# Sheet1.net
KiCad netlist of a schematic drawn in Altium Designer
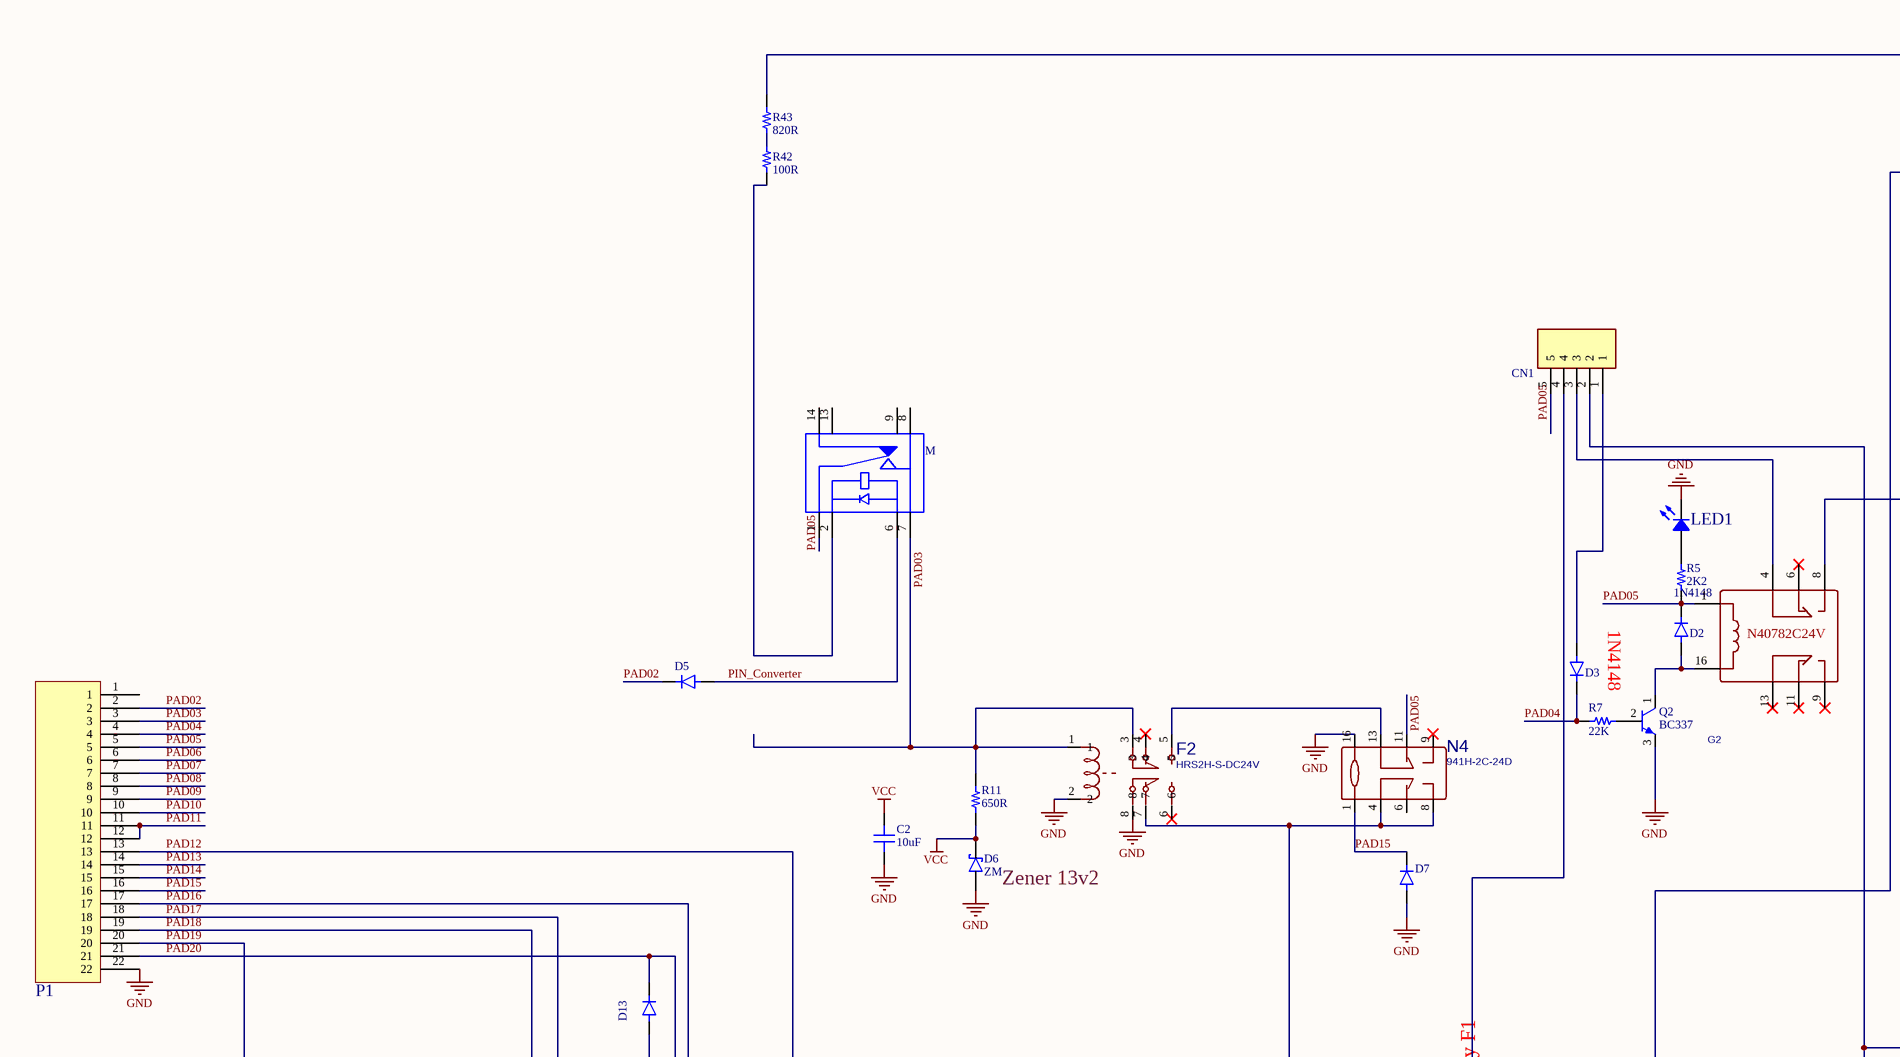
[diagram p0: Sheet1.SchDoc, top left]
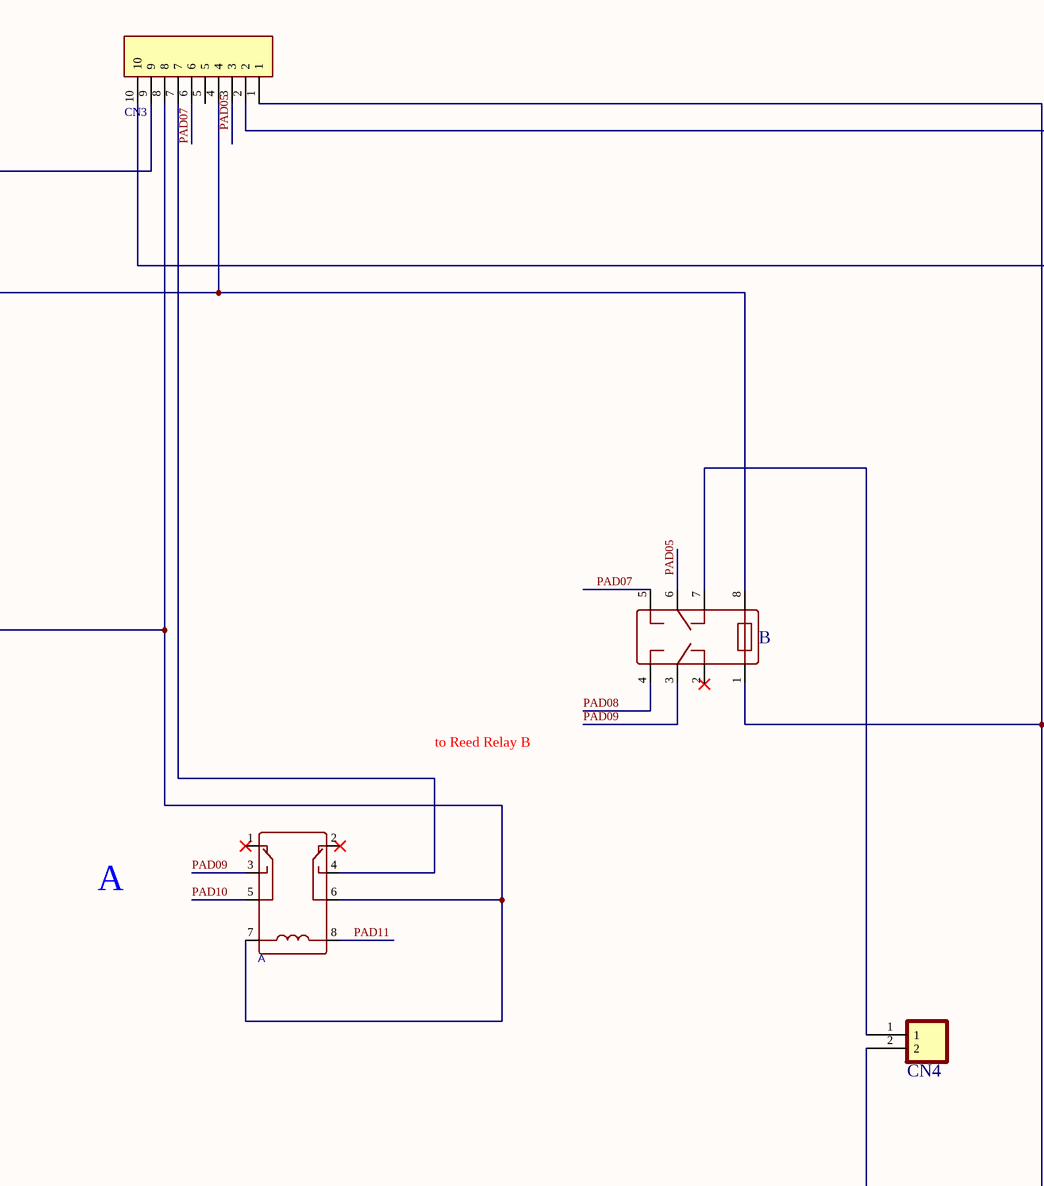
[diagram p1: Sheet1.SchDoc, top right]
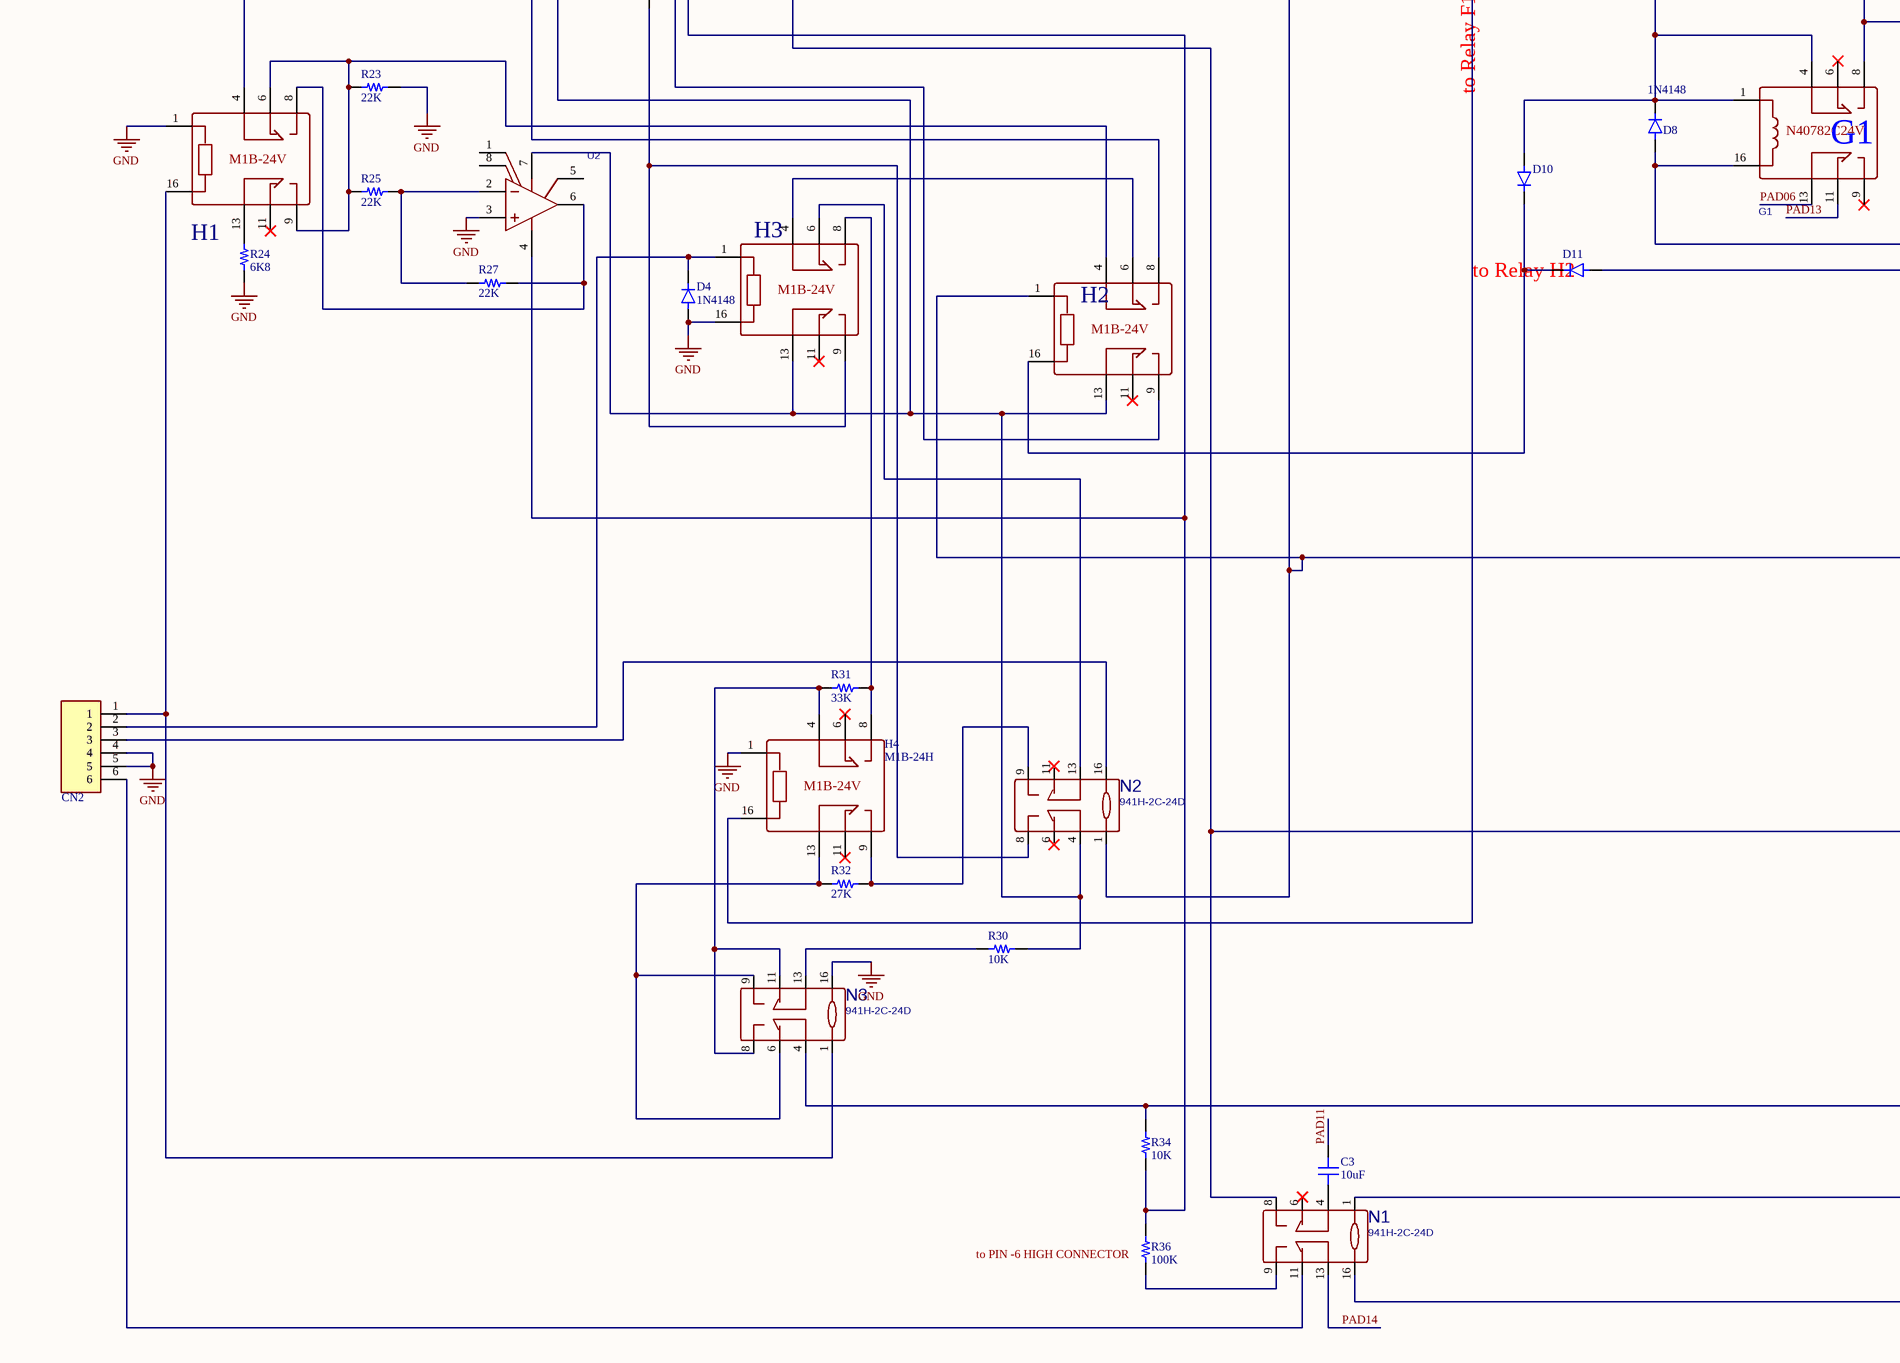
[diagram p2: Sheet1.SchDoc, bottom left]
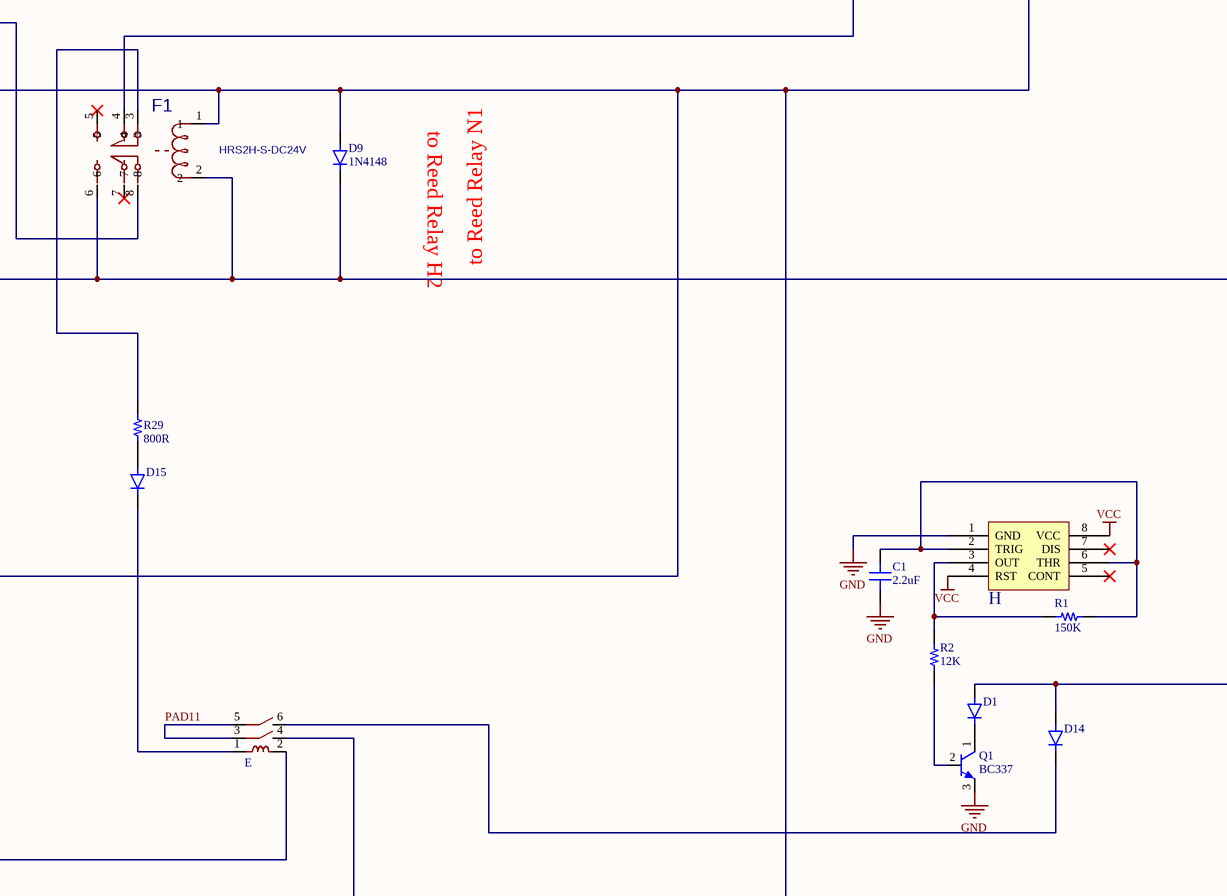
[diagram p3: Sheet1.SchDoc, bottom right]

(export (version "E")
  (design (tool "Eeschema 10.0.6"))
  (components
    (comp (ref "A")
      (value "OMRON_LY2")
      (footprint "OMRON_LY2")
      (fields
        (field (name "MANUFACTURER") "NF(福特)")
        (field (name "MANUFACTURER PART") "N40782C12V0.2W")
        (field (name "CONTRIBUTOR") "lcsc")
      )
      (libsource (lib "My Library") (part "OMRON_LY2"))
    )
    (comp (ref "B")
      (value "942H-2C-24DC")
      (footprint "942H-2C-24DC")
      (description "Relay 2C 24VDC")
      (libsource (lib "My Library") (part "942H-2C-24DC"))
    )
    (comp (ref "C1")
      (value "2.2uF")
      (footprint "Cap0805")
      (description "Cap 0805 2.2uF")
      (fields (field (name "PART NUMBER") "Cap-0805-2.2uF") (field (name "MANUFACTURER") "---"))
      (libsource (lib "My Library") (part "Unpolarised Capacitor"))
    )
    (comp (ref "C2")
      (value "10uF")
      (footprint "Cap0805")
      (description "Cap 0805 10uF")
      (fields (field (name "PART NUMBER") "Cap-0805-10uF") (field (name "MANUFACTURER") "---"))
      (libsource (lib "My Library") (part "Unpolarised Capacitor"))
    )
    (comp (ref "C3")
      (value "10uF")
      (footprint "Cap0805")
      (description "Cap 0805 10uF")
      (fields (field (name "PART NUMBER") "Cap-0805-10uF") (field (name "MANUFACTURER") "---"))
      (libsource (lib "My Library") (part "Unpolarised Capacitor"))
    )
    (comp (ref "CN1")
      (value "HDR5")
      (footprint "HDR5_F")
      (description "Pitch 2.54 mm 5PIN Femail")
      (fields (field (name "MP") "HTSW-105-14-L-S") (field (name "PART NUMBER") "PinHeader 5pin"))
      (libsource (lib "My Library") (part "HDR5_F"))
    )
    (comp (ref "CN2")
      (value "HDR6")
      (footprint "HDR6_F")
      (description "Pitch 2.54 mm")
      (fields (field (name "MP") "HTSW-106-07-S-S") (field (name "PART NUMBER") "PinHeader 6pin"))
      (libsource (lib "My Library") (part "HDR6_F"))
    )
    (comp (ref "CN3")
      (value "HDR10")
      (footprint "HDR10_F")
      (description "Pitch 2.54 mm")
      (fields (field (name "MP") "HTSW-106-07-S-S") (field (name "PART NUMBER") "PinHeader 10pin"))
      (libsource (lib "My Library") (part "HDR10_F"))
    )
    (comp (ref "CN4")
      (value "PWR_HDR_2P")
      (footprint "PWR_HDR_2P")
      (description "P-P= 3.96mm")
      (fields (field (name "PART NUMBER") "Power Connector"))
      (libsource (lib "My Library") (part "PWR_HDR_2P"))
    )
    (comp (ref "D1")
      (value "~")
      (footprint "SOD-123")
      (description "Diode Standard 75 V 300mA (DC) Through Hole DO-35 Mimi Melf")
      (fields (field (name "MP") "1N4148") (field (name "MF") "ON Semiconductor"))
      (libsource (lib "My Library") (part "Diode"))
    )
    (comp (ref "D2")
      (value "1N4148")
      (footprint "SOD-123")
      (description "Diode Standard 75 V 300mA (DC) Through Hole DO-35 Mimi Melf")
      (fields (field (name "MF") "ON Semiconductor"))
      (libsource (lib "My Library") (part "Diode"))
    )
    (comp (ref "D3")
      (value "~")
      (footprint "SOD-123")
      (description "Diode Standard 75 V 300mA (DC) Through Hole DO-35 Mimi Melf")
      (fields (field (name "MF") "ON Semiconductor") (field (name "MP") "1N4148"))
      (libsource (lib "My Library") (part "Diode"))
    )
    (comp (ref "D4")
      (value "1N4148")
      (footprint "SOD-123")
      (description "Diode Standard 75 V 300mA (DC) Through Hole DO-35 Mimi Melf")
      (fields (field (name "MF") "ON Semiconductor"))
      (libsource (lib "My Library") (part "Diode"))
    )
    (comp (ref "D5")
      (value "~")
      (footprint "SOD-123")
      (description "Diode Standard 75 V 300mA (DC) Through Hole DO-35 Mimi Melf")
      (fields (field (name "MF") "ON Semiconductor") (field (name "MP") "1N4148"))
      (libsource (lib "My Library") (part "Diode"))
    )
    (comp (ref "D6")
      (value "ZM")
      (footprint "Melf")
      (description "Zener Diode Melf")
      (fields (field (name "MP") "TMMBAT41") (field (name "MF") "STMicroelectronics"))
      (libsource (lib "My Library") (part "Zener"))
    )
    (comp (ref "D7")
      (value "~")
      (footprint "SOD-123")
      (description "Diode Standard 75 V 300mA (DC) Through Hole DO-35 Mimi Melf")
      (fields (field (name "MP") "1N4148") (field (name "MF") "ON Semiconductor"))
      (libsource (lib "My Library") (part "Diode"))
    )
    (comp (ref "D8")
      (value "1N4148")
      (footprint "SOD-123")
      (description "Diode Standard 75 V 300mA (DC) Through Hole DO-35 Mimi Melf")
      (fields (field (name "MF") "ON Semiconductor"))
      (libsource (lib "My Library") (part "Diode"))
    )
    (comp (ref "D9")
      (value "1N4148")
      (footprint "SOD-123")
      (description "Diode Standard 75 V 300mA (DC) Through Hole DO-35 Mimi Melf")
      (fields (field (name "MF") "ON Semiconductor"))
      (libsource (lib "My Library") (part "Diode"))
    )
    (comp (ref "D10")
      (value "~")
      (footprint "SOD-123")
      (description "Diode Standard 75 V 300mA (DC) Through Hole DO-35 Mimi Melf")
      (fields (field (name "MP") "1N4148") (field (name "MF") "ON Semiconductor"))
      (libsource (lib "My Library") (part "Diode"))
    )
    (comp (ref "D11")
      (value "~")
      (footprint "SOD-123")
      (description "Diode Standard 75 V 300mA (DC) Through Hole DO-35 Mimi Melf")
      (fields (field (name "MP") "1N4148") (field (name "MF") "ON Semiconductor"))
      (libsource (lib "My Library") (part "Diode"))
    )
    (comp (ref "D13")
      (value "~")
      (footprint "SOD-123")
      (description "Diode Standard 75 V 300mA (DC) Through Hole DO-35 Mimi Melf")
      (fields (field (name "MF") "ON Semiconductor") (field (name "MP") "1N4148"))
      (libsource (lib "My Library") (part "Diode"))
    )
    (comp (ref "D14")
      (value "~")
      (footprint "SOD-123")
      (description "Diode Standard 75 V 300mA (DC) Through Hole DO-35 Mimi Melf")
      (fields (field (name "MP") "1N4148") (field (name "MF") "ON Semiconductor"))
      (libsource (lib "My Library") (part "Diode"))
    )
    (comp (ref "D15")
      (value "~")
      (footprint "SOD-123")
      (description "Diode Standard 75 V 300mA (DC) Through Hole DO-35 Mimi Melf")
      (fields (field (name "MP") "1N4148") (field (name "MF") "ON Semiconductor"))
      (libsource (lib "My Library") (part "Diode"))
    )
    (comp (ref "E")
      (value "OL-C-212H")
      (footprint "ol-c-212H")
      (description "REED RELAY  2 Contact")
      (libsource (lib "My Library") (part "ol-c-212H"))
    )
    (comp (ref "F1")
      (value "HRS2H-S-DC24V")
      (footprint "HRS2H-S-DC24V")
      (fields (field (name "MANUFACTURER") "HKE(汇港)"))
      (libsource (lib "RezanFelez") (part "HRS2H-S-DC24V"))
    )
    (comp (ref "F2")
      (value "HRS2H-S-DC24V")
      (footprint "HRS2H-S-DC24V")
      (fields (field (name "MANUFACTURER") "HKE(汇港)"))
      (libsource (lib "") (part "HRS2H-S-DC24V_1"))
    )
    (comp (ref "G1")
      (value "N40782C12V0.2W")
      (footprint "N40782CXXXXX")
      (fields (field (name "MANUFACTURER") "NF(福特)") (field (name "CONTRIBUTOR") "lcsc"))
      (libsource (lib "Relay") (part "N40782C24V0.2W"))
    )
    (comp (ref "G2")
      (value "N40782C12V0.2W")
      (footprint "N40782CXXXXX")
      (fields (field (name "MANUFACTURER") "NF(福特)") (field (name "CONTRIBUTOR") "lcsc"))
      (libsource (lib "Relay") (part "N40782C24V0.2W"))
    )
    (comp (ref "H")
      (value "NE555P")
      (footprint "SOP8")
      (description "Astable or Monostable Operation")
      (fields (field (name "MANUFACTURER") "TI"))
      (libsource (lib "My Library") (part "NE555P"))
    )
    (comp (ref "H1") (value "M1B-24H") (footprint "M1B-24H") (libsource (lib "Relay") (part "M1B-24H")))
    (comp (ref "H2") (value "M1B-24H") (footprint "M1B-24H") (libsource (lib "Relay") (part "M1B-24H")))
    (comp (ref "H3") (value "M1B-24H") (footprint "M1B-24H") (libsource (lib "Relay") (part "M1B-24H")))
    (comp (ref "H4") (value "M1B-24H") (footprint "M1B-24H") (libsource (lib "Relay") (part "M1B-24H")))
    (comp (ref "LED1")
      (value "---")
      (footprint "0805 LED")
      (description "LED 0805 Red 635nm, Forward Current: 20mA, Forward Voltage: 1.7V")
      (fields (field (name "PART NUMBER") "598-8110-107F") (field (name "MANUFACTURER") "Dialight"))
      (libsource (lib "My Library") (part "LED"))
    )
    (comp (ref "M")
      (value "HE721R0510")
      (footprint "HE721R0510")
      (description "RELAY REED SPDT 250MA 5V")
      (fields (field (name "DIGI-KEY_PART_NUMBER") "F11467-ND") (field (name "MF") "Littelfuse Inc."))
      (libsource (lib "My Library") (part "HE721R0510"))
    )
    (comp (ref "N1")
      (value "941H-2C-24D")
      (footprint "941H-2C-24D")
      (fields (field (name "MANUFACTURER") "欣大") (field (name "CONTRIBUTOR") "LCSC"))
      (libsource (lib "RezanFelez") (part "941H-2C-24D"))
    )
    (comp (ref "N2")
      (value "941H-2C-24D")
      (footprint "941H-2C-24D")
      (fields (field (name "MANUFACTURER") "欣大") (field (name "CONTRIBUTOR") "LCSC"))
      (libsource (lib "RezanFelez") (part "941H-2C-24D"))
    )
    (comp (ref "N3")
      (value "941H-2C-24D")
      (footprint "941H-2C-24D")
      (fields (field (name "MANUFACTURER") "欣大") (field (name "CONTRIBUTOR") "LCSC"))
      (libsource (lib "RezanFelez") (part "941H-2C-24D"))
    )
    (comp (ref "N4")
      (value "941H-2C-24D")
      (footprint "941H-2C-24D")
      (fields (field (name "MANUFACTURER") "欣大") (field (name "CONTRIBUTOR") "LCSC"))
      (libsource (lib "RezanFelez") (part "941H-2C-24D"))
    )
    (comp (ref "P1")
      (value "PCI")
      (footprint "PCI")
      (description "normal PAD for SPARK project")
      (libsource (lib "My Library") (part "PCI"))
    )
    (comp (ref "Q1")
      (value "BC337")
      (footprint "TO92")
      (description "Transistor")
      (fields (field (name "MANUFACTURER") "Diodes-Incorporated"))
      (libsource (lib "My Library") (part "BJT-NPN"))
    )
    (comp (ref "Q2")
      (value "BC337")
      (footprint "TO92")
      (description "Transistor")
      (fields (field (name "MANUFACTURER") "Diodes-Incorporated"))
      (libsource (lib "My Library") (part "BJT-NPN"))
    )
    (comp (ref "R1")
      (value "150K")
      (footprint "Res1206")
      (description "Resistor 1206 150 Kohm")
      (fields (field (name "PART NUMBER") "Res-1206-150K"))
      (libsource (lib "My Library") (part "Resistor"))
    )
    (comp (ref "R2")
      (value "12K")
      (footprint "Res1206")
      (description "Resistor 1206 12 Kohm")
      (fields (field (name "PART NUMBER") "Res-1206-12K"))
      (libsource (lib "My Library") (part "Resistor"))
    )
    (comp (ref "R5")
      (value "2K2")
      (footprint "Res1206")
      (description "Resistor 1206 2.2 Kohm")
      (fields (field (name "PART NUMBER") "Res-1206-2K2"))
      (libsource (lib "My Library") (part "Resistor"))
    )
    (comp (ref "R7")
      (value "22K")
      (footprint "Res1206")
      (description "Resistor 1206 22 Kohm")
      (fields (field (name "PART NUMBER") "Res-1206-22K"))
      (libsource (lib "My Library") (part "Resistor"))
    )
    (comp (ref "R11")
      (value "650R")
      (footprint "Res1206")
      (description "Resistor 1206 650 ohm")
      (fields (field (name "PART NUMBER") "Res-1206-650R"))
      (libsource (lib "My Library") (part "Resistor"))
    )
    (comp (ref "R23")
      (value "22K")
      (footprint "Res1206")
      (description "Resistor 1206 22 Kohm")
      (fields (field (name "PART NUMBER") "Res-1206-22K"))
      (libsource (lib "My Library") (part "Resistor"))
    )
    (comp (ref "R24")
      (value "6K8")
      (footprint "Res1206")
      (description "Resistor 1206 6.8 Kohm")
      (fields (field (name "PART NUMBER") "Res-1206-6K8"))
      (libsource (lib "My Library") (part "Resistor"))
    )
    (comp (ref "R25")
      (value "22K")
      (footprint "Res1206")
      (description "Resistor 1206 22 Kohm")
      (fields (field (name "PART NUMBER") "Res-1206-22K"))
      (libsource (lib "My Library") (part "Resistor"))
    )
    (comp (ref "R27")
      (value "22K")
      (footprint "Res1206")
      (description "Resistor 1206 22 Kohm")
      (fields (field (name "PART NUMBER") "Res-1206-22K"))
      (libsource (lib "My Library") (part "Resistor"))
    )
    (comp (ref "R29")
      (value "800R")
      (footprint "Res1206")
      (description "Resistor 1206 800 ohm")
      (fields (field (name "PART NUMBER") "Res-1206-800R"))
      (libsource (lib "My Library") (part "Resistor"))
    )
    (comp (ref "R30")
      (value "10K")
      (footprint "Res1206")
      (description "Resistor 1206 10 Kohm")
      (fields (field (name "PART NUMBER") "Res-1206-10K") (field (name "MANUFACTURER") "---"))
      (libsource (lib "My Library") (part "Resistor"))
    )
    (comp (ref "R31")
      (value "33K")
      (footprint "Res1206")
      (description "Resistor 1206 33 Kohm")
      (fields (field (name "PART NUMBER") "Res-1206-33K"))
      (libsource (lib "My Library") (part "Resistor"))
    )
    (comp (ref "R32")
      (value "27K")
      (footprint "Res1206")
      (description "Resistor 1206 27 Kohm")
      (fields (field (name "PART NUMBER") "Res-1206-27K"))
      (libsource (lib "My Library") (part "Resistor"))
    )
    (comp (ref "R34")
      (value "10K")
      (footprint "Res1206")
      (description "Resistor 1206 10 Kohm")
      (fields (field (name "PART NUMBER") "Res-1206-10K") (field (name "MANUFACTURER") "---"))
      (libsource (lib "My Library") (part "Resistor"))
    )
    (comp (ref "R36")
      (value "100K")
      (footprint "Res1206")
      (fields (field (name "PART NUMBER") "Res-1206-100K") (field (name "MANUFACTURER") "---"))
      (libsource (lib "My Library") (part "Resistor"))
    )
    (comp (ref "R42")
      (value "100R")
      (footprint "Res1206")
      (description "Resistor 1206 100 ohm")
      (fields (field (name "PART NUMBER") "Res-1206-100R"))
      (libsource (lib "My Library") (part "Resistor"))
    )
    (comp (ref "R43")
      (value "820R")
      (footprint "Res1206")
      (description "Resistor 1206 820 ohm")
      (fields (field (name "PART NUMBER") "Res-1206-820R"))
      (libsource (lib "My Library") (part "Resistor"))
    )
    (comp (ref "U2")
      (value "OP07CP")
      (footprint "SOP8")
      (description "OPAMP")
      (fields (field (name "MANUFACTURER") "TI"))
      (libsource (lib "My Library") (part "OP07CP"))
    )
  )
  (nets
    (net (code "1") (name "/PAD02") (class "Default")
      (node (ref "D5") (pin "C") (pinfunction "C_C") (pintype "passive"))
      (node (ref "P1") (pin "2") (pinfunction "2_2") (pintype "passive"))
    )
    (net (code "2") (name "/PAD03") (class "Default")
      (node (ref "F2") (pin "1") (pinfunction "1_1") (pintype "passive"))
      (node (ref "F2") (pin "3") (pinfunction "3_3") (pintype "passive"))
      (node (ref "M") (pin "7") (pinfunction "7_7") (pintype "passive"))
      (node (ref "P1") (pin "3") (pinfunction "3_3") (pintype "passive"))
      (node (ref "R11") (pin "2") (pinfunction "2_2") (pintype "passive"))
    )
    (net (code "3") (name "/PAD04") (class "Default")
      (node (ref "D3") (pin "C") (pinfunction "C_C") (pintype "passive"))
      (node (ref "P1") (pin "4") (pinfunction "4_4") (pintype "passive"))
      (node (ref "R7") (pin "1") (pinfunction "1_1") (pintype "passive"))
    )
    (net (code "4") (name "/PAD05") (class "Default")
      (node (ref "B") (pin "6") (pinfunction "6_6") (pintype "passive"))
      (node (ref "CN1") (pin "5") (pinfunction "5_5") (pintype "passive"))
      (node (ref "CN3") (pin "3") (pinfunction "3_3") (pintype "passive"))
      (node (ref "D2") (pin "C") (pinfunction "C_C") (pintype "passive"))
      (node (ref "G2") (pin "1") (pinfunction "1_1") (pintype "passive"))
      (node (ref "M") (pin "1") (pinfunction "1_1") (pintype "passive"))
      (node (ref "N4") (pin "11") (pinfunction "11_11") (pintype "passive"))
      (node (ref "P1") (pin "5") (pinfunction "5_5") (pintype "passive"))
      (node (ref "R5") (pin "1") (pinfunction "1_1") (pintype "passive"))
    )
    (net (code "5") (name "/PAD06") (class "Default")
      (node (ref "G1") (pin "13") (pinfunction "13_13") (pintype "passive"))
      (node (ref "P1") (pin "6") (pinfunction "6_6") (pintype "passive"))
    )
    (net (code "6") (name "/PAD07") (class "Default")
      (node (ref "B") (pin "5") (pinfunction "5_5") (pintype "passive"))
      (node (ref "CN3") (pin "6") (pinfunction "6_6") (pintype "passive"))
      (node (ref "P1") (pin "7") (pinfunction "7_7") (pintype "passive"))
    )
    (net (code "7") (name "/PAD08") (class "Default")
      (node (ref "B") (pin "4") (pinfunction "4_4") (pintype "passive"))
      (node (ref "P1") (pin "8") (pinfunction "8_8") (pintype "passive"))
    )
    (net (code "8") (name "/PAD09") (class "Default")
      (node (ref "A") (pin "3") (pinfunction "3_3") (pintype "passive"))
      (node (ref "B") (pin "3") (pinfunction "3_3") (pintype "passive"))
      (node (ref "P1") (pin "9") (pinfunction "9_9") (pintype "passive"))
    )
    (net (code "9") (name "/PAD10") (class "Default")
      (node (ref "A") (pin "5") (pinfunction "5_5") (pintype "passive"))
      (node (ref "P1") (pin "10") (pinfunction "10_10") (pintype "passive"))
    )
    (net (code "10") (name "/PAD11") (class "Default")
      (node (ref "A") (pin "8") (pinfunction "8_8") (pintype "passive"))
      (node (ref "C3") (pin "2") (pinfunction "2_2") (pintype "passive"))
      (node (ref "E") (pin "3") (pinfunction "3_3") (pintype "passive"))
      (node (ref "E") (pin "5") (pinfunction "5_5") (pintype "passive"))
      (node (ref "P1") (pin "11") (pinfunction "11_11") (pintype "passive"))
      (node (ref "P1") (pin "12") (pinfunction "12_12") (pintype "passive"))
    )
    (net (code "11") (name "/PAD12") (class "Default")
      (node (ref "E") (pin "2") (pinfunction "2_2") (pintype "passive"))
      (node (ref "N1") (pin "8") (pinfunction "8_8") (pintype "passive"))
      (node (ref "P1") (pin "13") (pinfunction "13_13") (pintype "passive"))
    )
    (net (code "12") (name "/PAD13") (class "Default")
      (node (ref "G1") (pin "11") (pinfunction "11_11") (pintype "passive"))
      (node (ref "P1") (pin "14") (pinfunction "14_14") (pintype "passive"))
    )
    (net (code "13") (name "/PAD14") (class "Default")
      (node (ref "N1") (pin "13") (pinfunction "13_13") (pintype "passive"))
      (node (ref "P1") (pin "15") (pinfunction "15_15") (pintype "passive"))
    )
    (net (code "14") (name "/PAD15") (class "Default")
      (node (ref "D7") (pin "C") (pinfunction "C_C") (pintype "passive"))
      (node (ref "N4") (pin "1") (pinfunction "1_1") (pintype "passive"))
      (node (ref "P1") (pin "16") (pinfunction "16_16") (pintype "passive"))
    )
    (net (code "15") (name "/PAD16") (class "Default")
      (node (ref "P1") (pin "17") (pinfunction "17_17") (pintype "passive"))
      (node (ref "R34") (pin "2") (pinfunction "2_2") (pintype "passive"))
      (node (ref "R36") (pin "1") (pinfunction "1_1") (pintype "passive"))
      (node (ref "U2") (pin "4") (pinfunction "4_4") (pintype "passive"))
    )
    (net (code "16") (name "/PAD17") (class "Default")
      (node (ref "H2") (pin "13") (pinfunction "13_13") (pintype "passive"))
      (node (ref "H3") (pin "13") (pinfunction "13_13") (pintype "passive"))
      (node (ref "N2") (pin "4") (pinfunction "4_4") (pintype "passive"))
      (node (ref "P1") (pin "18") (pinfunction "18_18") (pintype "passive"))
      (node (ref "R30") (pin "2") (pinfunction "2_2") (pintype "passive"))
      (node (ref "U2") (pin "7") (pinfunction "7_7") (pintype "passive"))
    )
    (net (code "17") (name "/PAD18") (class "Default")
      (node (ref "H2") (pin "8") (pinfunction "8_8") (pintype "passive"))
      (node (ref "P1") (pin "19") (pinfunction "19_19") (pintype "passive"))
    )
    (net (code "18") (name "/PAD19") (class "Default")
      (node (ref "H1") (pin "4") (pinfunction "4_4") (pintype "passive"))
      (node (ref "P1") (pin "20") (pinfunction "20_20") (pintype "passive"))
    )
    (net (code "19") (name "/PAD20") (class "Default")
      (node (ref "D13") (pin "C") (pinfunction "C_C") (pintype "passive"))
      (node (ref "H2") (pin "9") (pinfunction "9_9") (pintype "passive"))
      (node (ref "P1") (pin "21") (pinfunction "21_21") (pintype "passive"))
    )
    (net (code "20") (name "/PIN_Converter") (class "Default")
      (node (ref "D5") (pin "A") (pinfunction "A_A") (pintype "passive"))
      (node (ref "M") (pin "6") (pinfunction "6_6") (pintype "passive"))
    )
    (net (code "21") (name "GND") (class "Default")
      (node (ref "C1") (pin "1") (pinfunction "1_1") (pintype "passive"))
      (node (ref "C2") (pin "1") (pinfunction "1_1") (pintype "passive"))
      (node (ref "CN2") (pin "4") (pinfunction "4_4") (pintype "passive"))
      (node (ref "CN2") (pin "5") (pinfunction "5_5") (pintype "passive"))
      (node (ref "D4") (pin "A") (pinfunction "A_A") (pintype "passive"))
      (node (ref "D6") (pin "A") (pinfunction "A_A") (pintype "passive"))
      (node (ref "D7") (pin "A") (pinfunction "A_A") (pintype "passive"))
      (node (ref "F2") (pin "2") (pinfunction "2_2") (pintype "passive"))
      (node (ref "F2") (pin "8") (pinfunction "8_8") (pintype "passive"))
      (node (ref "H") (pin "1") (pinfunction "GND_1") (pintype "passive"))
      (node (ref "H1") (pin "1") (pinfunction "1_1") (pintype "passive"))
      (node (ref "H3") (pin "16") (pinfunction "16_16") (pintype "passive"))
      (node (ref "H4") (pin "1") (pinfunction "1_1") (pintype "passive"))
      (node (ref "LED1") (pin "2") (pinfunction "2_2") (pintype "passive"))
      (node (ref "N3") (pin "16") (pinfunction "16_16") (pintype "passive"))
      (node (ref "N4") (pin "16") (pinfunction "16_16") (pintype "passive"))
      (node (ref "P1") (pin "22") (pinfunction "22_22") (pintype "passive"))
      (node (ref "Q1") (pin "3") (pinfunction "E_3") (pintype "passive"))
      (node (ref "Q2") (pin "3") (pinfunction "E_3") (pintype "passive"))
      (node (ref "R23") (pin "2") (pinfunction "2_2") (pintype "passive"))
      (node (ref "R24") (pin "2") (pinfunction "2_2") (pintype "passive"))
      (node (ref "U2") (pin "3") (pinfunction "3_3") (pintype "passive"))
    )
    (net (code "22") (name "Net-(A-Pad4)") (class "Default")
      (node (ref "A") (pin "4") (pinfunction "4_4") (pintype "passive"))
      (node (ref "CN3") (pin "7") (pinfunction "7_7") (pintype "passive"))
    )
    (net (code "23") (name "Net-(A-Pad6)") (class "Default")
      (node (ref "A") (pin "6") (pinfunction "6_6") (pintype "passive"))
      (node (ref "A") (pin "7") (pinfunction "7_7") (pintype "passive"))
      (node (ref "CN3") (pin "8") (pinfunction "8_8") (pintype "passive"))
      (node (ref "G2") (pin "8") (pinfunction "8_8") (pintype "passive"))
    )
    (net (code "24") (name "Net-(B-Pad1)") (class "Default")
      (node (ref "B") (pin "1") (pinfunction "1_1") (pintype "passive"))
      (node (ref "CN3") (pin "1") (pinfunction "1_1") (pintype "passive"))
      (node (ref "D8") (pin "A") (pinfunction "A_A") (pintype "passive"))
      (node (ref "D9") (pin "A") (pinfunction "A_A") (pintype "passive"))
      (node (ref "F1") (pin "1") (pinfunction "1_1") (pintype "passive"))
      (node (ref "F2") (pin "7") (pinfunction "7_7") (pintype "passive"))
      (node (ref "G1") (pin "16") (pinfunction "16_16") (pintype "passive"))
      (node (ref "H2") (pin "1") (pinfunction "1_1") (pintype "passive"))
      (node (ref "N1") (pin "16") (pinfunction "16_16") (pintype "passive"))
      (node (ref "N2") (pin "1") (pinfunction "1_1") (pintype "passive"))
      (node (ref "N4") (pin "4") (pinfunction "4_4") (pintype "passive"))
      (node (ref "N4") (pin "8") (pinfunction "8_8") (pintype "passive"))
    )
    (net (code "25") (name "Net-(B-Pad7)") (class "Default")
      (node (ref "B") (pin "7") (pinfunction "7_7") (pintype "passive"))
      (node (ref "CN4") (pin "1") (pinfunction "1_1") (pintype "passive"))
    )
    (net (code "26") (name "Net-(B-Pad8)") (class "Default")
      (node (ref "B") (pin "8") (pinfunction "8_8") (pintype "passive"))
      (node (ref "CN3") (pin "4") (pinfunction "4_4") (pintype "passive"))
      (node (ref "D10") (pin "A") (pinfunction "A_A") (pintype "passive"))
      (node (ref "D8") (pin "C") (pinfunction "C_C") (pintype "passive"))
      (node (ref "G1") (pin "1") (pinfunction "1_1") (pintype "passive"))
      (node (ref "G1") (pin "4") (pinfunction "4_4") (pintype "passive"))
    )
    (net (code "27") (name "Net-(C3-Pad1)") (class "Default")
      (node (ref "C3") (pin "1") (pinfunction "1_1") (pintype "passive"))
      (node (ref "N1") (pin "4") (pinfunction "4_4") (pintype "passive"))
    )
    (net (code "28") (name "Net-(CN1-Pad1)") (class "Default")
      (node (ref "CN1") (pin "1") (pinfunction "1_1") (pintype "passive"))
      (node (ref "D3") (pin "A") (pinfunction "A_A") (pintype "passive"))
    )
    (net (code "29") (name "Net-(CN1-Pad2)") (class "Default")
      (node (ref "CN1") (pin "2") (pinfunction "2_2") (pintype "passive"))
      (node (ref "F1") (pin "8") (pinfunction "8_8") (pintype "passive"))
      (node (ref "G1") (pin "8") (pinfunction "8_8") (pintype "passive"))
    )
    (net (code "30") (name "Net-(CN1-Pad3)") (class "Default")
      (node (ref "CN1") (pin "3") (pinfunction "3_3") (pintype "passive"))
      (node (ref "G2") (pin "4") (pinfunction "4_4") (pintype "passive"))
    )
    (net (code "31") (name "Net-(CN1-Pad4)") (class "Default")
      (node (ref "CN1") (pin "4") (pinfunction "4_4") (pintype "passive"))
      (node (ref "H4") (pin "16") (pinfunction "16_16") (pintype "passive"))
    )
    (net (code "32") (name "Net-(CN2-Pad1)") (class "Default")
      (node (ref "CN2") (pin "1") (pinfunction "1_1") (pintype "passive"))
      (node (ref "H1") (pin "16") (pinfunction "16_16") (pintype "passive"))
      (node (ref "N3") (pin "1") (pinfunction "1_1") (pintype "passive"))
    )
    (net (code "33") (name "Net-(CN2-Pad2)") (class "Default")
      (node (ref "CN2") (pin "2") (pinfunction "2_2") (pintype "passive"))
      (node (ref "D4") (pin "C") (pinfunction "C_C") (pintype "passive"))
      (node (ref "H3") (pin "1") (pinfunction "1_1") (pintype "passive"))
    )
    (net (code "34") (name "Net-(CN2-Pad3)") (class "Default")
      (node (ref "CN2") (pin "3") (pinfunction "3_3") (pintype "passive"))
      (node (ref "N2") (pin "16") (pinfunction "16_16") (pintype "passive"))
    )
    (net (code "35") (name "Net-(CN2-Pad6)") (class "Default")
      (node (ref "CN2") (pin "6") (pinfunction "6_6") (pintype "passive"))
      (node (ref "N1") (pin "11") (pinfunction "11_11") (pintype "passive"))
    )
    (net (code "36") (name "Net-(CN3-Pad2)") (class "Default")
      (node (ref "CN3") (pin "2") (pinfunction "2_2") (pintype "passive"))
      (node (ref "D1") (pin "A") (pinfunction "A_A") (pintype "passive"))
      (node (ref "D14") (pin "A") (pinfunction "A_A") (pintype "passive"))
    )
    (net (code "37") (name "Net-(CN3-Pad9)") (class "Default")
      (node (ref "CN3") (pin "9") (pinfunction "9_9") (pintype "passive"))
      (node (ref "R43") (pin "2") (pinfunction "2_2") (pintype "passive"))
    )
    (net (code "38") (name "Net-(CN3-Pad10)") (class "Default")
      (node (ref "CN3") (pin "10") (pinfunction "10_10") (pintype "passive"))
      (node (ref "D11") (pin "A") (pinfunction "A_A") (pintype "passive"))
      (node (ref "D9") (pin "C") (pinfunction "C_C") (pintype "passive"))
      (node (ref "F1") (pin "2") (pinfunction "2_2") (pintype "passive"))
      (node (ref "F1") (pin "6") (pinfunction "6_6") (pintype "passive"))
      (node (ref "N1") (pin "1") (pinfunction "1_1") (pintype "passive"))
    )
    (net (code "39") (name "Net-(CN4-Pad2)") (class "Default")
      (node (ref "CN4") (pin "2") (pinfunction "2_2") (pintype "passive"))
      (node (ref "F1") (pin "4") (pinfunction "4_4") (pintype "passive"))
    )
    (net (code "40") (name "Net-(D10-PadC)") (class "Default")
      (node (ref "D10") (pin "C") (pinfunction "C_C") (pintype "passive"))
      (node (ref "D11") (pin "C") (pinfunction "C_C") (pintype "passive"))
      (node (ref "H2") (pin "16") (pinfunction "16_16") (pintype "passive"))
    )
    (net (code "41") (name "Net-(D13-PadA)") (class "Default")
      (node (ref "D13") (pin "A") (pinfunction "A_A") (pintype "passive"))
      (node (ref "H3") (pin "9") (pinfunction "9_9") (pintype "passive"))
      (node (ref "N2") (pin "8") (pinfunction "8_8") (pintype "passive"))
    )
    (net (code "42") (name "Net-(D14-PadC)") (class "Default")
      (node (ref "D14") (pin "C") (pinfunction "C_C") (pintype "passive"))
      (node (ref "E") (pin "6") (pinfunction "6_6") (pintype "passive"))
    )
    (net (code "43") (name "Net-(D15-PadA)") (class "Default")
      (node (ref "D15") (pin "A") (pinfunction "A_A") (pintype "passive"))
      (node (ref "R29") (pin "2") (pinfunction "2_2") (pintype "passive"))
    )
    (net (code "44") (name "Net-(D15-PadC)") (class "Default")
      (node (ref "D15") (pin "C") (pinfunction "C_C") (pintype "passive"))
      (node (ref "E") (pin "1") (pinfunction "1_1") (pintype "passive"))
    )
    (net (code "45") (name "Net-(E-Pad4)") (class "Default")
      (node (ref "E") (pin "4") (pinfunction "4_4") (pintype "passive"))
      (node (ref "N3") (pin "4") (pinfunction "4_4") (pintype "passive"))
      (node (ref "R34") (pin "1") (pinfunction "1_1") (pintype "passive"))
    )
    (net (code "46") (name "Net-(F1-Pad3)") (class "Default")
      (node (ref "F1") (pin "3") (pinfunction "3_3") (pintype "passive"))
      (node (ref "R29") (pin "1") (pinfunction "1_1") (pintype "passive"))
    )
    (net (code "47") (name "Net-(F2-Pad5)") (class "Default")
      (node (ref "F2") (pin "5") (pinfunction "5_5") (pintype "passive"))
      (node (ref "N4") (pin "13") (pinfunction "13_13") (pintype "passive"))
    )
    (net (code "48") (name "Net-(H-OUT)") (class "Default")
      (node (ref "H") (pin "3") (pinfunction "OUT_3") (pintype "passive"))
      (node (ref "R1") (pin "2") (pinfunction "2_2") (pintype "passive"))
      (node (ref "R2") (pin "2") (pinfunction "2_2") (pintype "passive"))
    )
    (net (code "49") (name "Net-(H-THR)") (class "Default")
      (node (ref "C1") (pin "2") (pinfunction "2_2") (pintype "passive"))
      (node (ref "H") (pin "2") (pinfunction "TRIG_2") (pintype "passive"))
      (node (ref "H") (pin "6") (pinfunction "THR_6") (pintype "passive"))
      (node (ref "R1") (pin "1") (pinfunction "1_1") (pintype "passive"))
    )
    (net (code "50") (name "Net-(H1-Pad6)") (class "Default")
      (node (ref "H1") (pin "6") (pinfunction "6_6") (pintype "passive"))
      (node (ref "H1") (pin "9") (pinfunction "9_9") (pintype "passive"))
      (node (ref "H2") (pin "4") (pinfunction "4_4") (pintype "passive"))
      (node (ref "R23") (pin "1") (pinfunction "1_1") (pintype "passive"))
      (node (ref "R25") (pin "1") (pinfunction "1_1") (pintype "passive"))
    )
    (net (code "51") (name "Net-(H1-Pad8)") (class "Default")
      (node (ref "H1") (pin "8") (pinfunction "8_8") (pintype "passive"))
      (node (ref "R27") (pin "1") (pinfunction "1_1") (pintype "passive"))
      (node (ref "U2") (pin "6") (pinfunction "6_6") (pintype "passive"))
    )
    (net (code "52") (name "Net-(H1-Pad13)") (class "Default")
      (node (ref "H1") (pin "13") (pinfunction "13_13") (pintype "passive"))
      (node (ref "R24") (pin "1") (pinfunction "1_1") (pintype "passive"))
    )
    (net (code "53") (name "Net-(H2-Pad6)") (class "Default")
      (node (ref "H2") (pin "6") (pinfunction "6_6") (pintype "passive"))
      (node (ref "H3") (pin "4") (pinfunction "4_4") (pintype "passive"))
    )
    (net (code "54") (name "Net-(H3-Pad6)") (class "Default")
      (node (ref "H3") (pin "6") (pinfunction "6_6") (pintype "passive"))
      (node (ref "N2") (pin "13") (pinfunction "13_13") (pintype "passive"))
    )
    (net (code "55") (name "Net-(H3-Pad8)") (class "Default")
      (node (ref "H3") (pin "8") (pinfunction "8_8") (pintype "passive"))
      (node (ref "H4") (pin "8") (pinfunction "8_8") (pintype "passive"))
      (node (ref "R31") (pin "1") (pinfunction "1_1") (pintype "passive"))
    )
    (net (code "56") (name "Net-(H4-Pad4)") (class "Default")
      (node (ref "H4") (pin "4") (pinfunction "4_4") (pintype "passive"))
      (node (ref "N3") (pin "11") (pinfunction "11_11") (pintype "passive"))
      (node (ref "N3") (pin "8") (pinfunction "8_8") (pintype "passive"))
      (node (ref "R31") (pin "2") (pinfunction "2_2") (pintype "passive"))
    )
    (net (code "57") (name "Net-(H4-Pad9)") (class "Default")
      (node (ref "H4") (pin "9") (pinfunction "9_9") (pintype "passive"))
      (node (ref "N2") (pin "9") (pinfunction "9_9") (pintype "passive"))
      (node (ref "R32") (pin "2") (pinfunction "2_2") (pintype "passive"))
    )
    (net (code "58") (name "Net-(H4-Pad13)") (class "Default")
      (node (ref "H4") (pin "13") (pinfunction "13_13") (pintype "passive"))
      (node (ref "N3") (pin "6") (pinfunction "6_6") (pintype "passive"))
      (node (ref "N3") (pin "9") (pinfunction "9_9") (pintype "passive"))
      (node (ref "R32") (pin "1") (pinfunction "1_1") (pintype "passive"))
    )
    (net (code "59") (name "Net-(LED1-Pad1)") (class "Default")
      (node (ref "LED1") (pin "1") (pinfunction "1_1") (pintype "passive"))
      (node (ref "R5") (pin "2") (pinfunction "2_2") (pintype "passive"))
    )
    (net (code "60") (name "Net-(M-Pad2)") (class "Default")
      (node (ref "M") (pin "2") (pinfunction "2_2") (pintype "passive"))
      (node (ref "R42") (pin "1") (pinfunction "1_1") (pintype "passive"))
    )
    (net (code "61") (name "Net-(N1-Pad9)") (class "Default")
      (node (ref "N1") (pin "9") (pinfunction "9_9") (pintype "passive"))
      (node (ref "R36") (pin "2") (pinfunction "2_2") (pintype "passive"))
    )
    (net (code "62") (name "Net-(N3-Pad13)") (class "Default")
      (node (ref "N3") (pin "13") (pinfunction "13_13") (pintype "passive"))
      (node (ref "R30") (pin "1") (pinfunction "1_1") (pintype "passive"))
    )
    (net (code "63") (name "Net-(Q1-B)") (class "Default")
      (node (ref "Q1") (pin "2") (pinfunction "B_2") (pintype "passive"))
      (node (ref "R2") (pin "1") (pinfunction "1_1") (pintype "passive"))
    )
    (net (code "64") (name "Net-(Q1-C)") (class "Default")
      (node (ref "D1") (pin "C") (pinfunction "C_C") (pintype "passive"))
      (node (ref "Q1") (pin "1") (pinfunction "C_1") (pintype "passive"))
    )
    (net (code "65") (name "Net-(Q2-B)") (class "Default")
      (node (ref "Q2") (pin "2") (pinfunction "B_2") (pintype "passive"))
      (node (ref "R7") (pin "2") (pinfunction "2_2") (pintype "passive"))
    )
    (net (code "66") (name "Net-(Q2-C)") (class "Default")
      (node (ref "D2") (pin "A") (pinfunction "A_A") (pintype "passive"))
      (node (ref "G2") (pin "16") (pinfunction "16_16") (pintype "passive"))
      (node (ref "Q2") (pin "1") (pinfunction "C_1") (pintype "passive"))
    )
    (net (code "67") (name "Net-(R25-Pad2)") (class "Default")
      (node (ref "R25") (pin "2") (pinfunction "2_2") (pintype "passive"))
      (node (ref "R27") (pin "2") (pinfunction "2_2") (pintype "passive"))
      (node (ref "U2") (pin "2") (pinfunction "2_2") (pintype "passive"))
    )
    (net (code "68") (name "Net-(R42-Pad2)") (class "Default")
      (node (ref "R42") (pin "2") (pinfunction "2_2") (pintype "passive"))
      (node (ref "R43") (pin "1") (pinfunction "1_1") (pintype "passive"))
    )
    (net (code "69") (name "VCC") (class "Default")
      (node (ref "C2") (pin "2") (pinfunction "2_2") (pintype "passive"))
      (node (ref "D6") (pin "C") (pinfunction "C_C") (pintype "passive"))
      (node (ref "H") (pin "4") (pinfunction "RST_4") (pintype "passive"))
      (node (ref "H") (pin "8") (pinfunction "VCC_8") (pintype "passive"))
      (node (ref "R11") (pin "1") (pinfunction "1_1") (pintype "passive"))
    )
    (net (code "70") (name "unconnected-(A-Pad1)") (class "Default")
      (node (ref "A") (pin "1") (pinfunction "1_1") (pintype "passive+no_connect"))
    )
    (net (code "71") (name "unconnected-(A-Pad2)") (class "Default")
      (node (ref "A") (pin "2") (pinfunction "2_2") (pintype "passive+no_connect"))
    )
    (net (code "72") (name "unconnected-(B-Pad2)") (class "Default")
      (node (ref "B") (pin "2") (pinfunction "2_2") (pintype "passive+no_connect"))
    )
    (net (code "73") (name "unconnected-(CN3-Pad5)") (class "Default")
      (node (ref "CN3") (pin "5") (pinfunction "5_5") (pintype "passive"))
    )
    (net (code "74") (name "unconnected-(F1-Pad5)") (class "Default")
      (node (ref "F1") (pin "5") (pinfunction "5_5") (pintype "passive+no_connect"))
    )
    (net (code "75") (name "unconnected-(F1-Pad7)") (class "Default")
      (node (ref "F1") (pin "7") (pinfunction "7_7") (pintype "passive+no_connect"))
    )
    (net (code "76") (name "unconnected-(F2-Pad4)") (class "Default")
      (node (ref "F2") (pin "4") (pinfunction "4_4") (pintype "passive+no_connect"))
    )
    (net (code "77") (name "unconnected-(F2-Pad6)") (class "Default")
      (node (ref "F2") (pin "6") (pinfunction "6_6") (pintype "passive+no_connect"))
    )
    (net (code "78") (name "unconnected-(G1-Pad6)") (class "Default")
      (node (ref "G1") (pin "6") (pinfunction "6_6") (pintype "passive+no_connect"))
    )
    (net (code "79") (name "unconnected-(G1-Pad9)") (class "Default")
      (node (ref "G1") (pin "9") (pinfunction "9_9") (pintype "passive+no_connect"))
    )
    (net (code "80") (name "unconnected-(G2-Pad6)") (class "Default")
      (node (ref "G2") (pin "6") (pinfunction "6_6") (pintype "passive+no_connect"))
    )
    (net (code "81") (name "unconnected-(G2-Pad9)") (class "Default")
      (node (ref "G2") (pin "9") (pinfunction "9_9") (pintype "passive+no_connect"))
    )
    (net (code "82") (name "unconnected-(G2-Pad11)") (class "Default")
      (node (ref "G2") (pin "11") (pinfunction "11_11") (pintype "passive+no_connect"))
    )
    (net (code "83") (name "unconnected-(G2-Pad13)") (class "Default")
      (node (ref "G2") (pin "13") (pinfunction "13_13") (pintype "passive+no_connect"))
    )
    (net (code "84") (name "unconnected-(H-CONT-Pad5)") (class "Default")
      (node (ref "H") (pin "5") (pinfunction "CONT_5") (pintype "passive+no_connect"))
    )
    (net (code "85") (name "unconnected-(H-DIS-Pad7)") (class "Default")
      (node (ref "H") (pin "7") (pinfunction "DIS_7") (pintype "passive+no_connect"))
    )
    (net (code "86") (name "unconnected-(H1-Pad11)") (class "Default")
      (node (ref "H1") (pin "11") (pinfunction "11_11") (pintype "passive+no_connect"))
    )
    (net (code "87") (name "unconnected-(H2-Pad11)") (class "Default")
      (node (ref "H2") (pin "11") (pinfunction "11_11") (pintype "passive+no_connect"))
    )
    (net (code "88") (name "unconnected-(H3-Pad11)") (class "Default")
      (node (ref "H3") (pin "11") (pinfunction "11_11") (pintype "passive+no_connect"))
    )
    (net (code "89") (name "unconnected-(H4-Pad6)") (class "Default")
      (node (ref "H4") (pin "6") (pinfunction "6_6") (pintype "passive+no_connect"))
    )
    (net (code "90") (name "unconnected-(H4-Pad11)") (class "Default")
      (node (ref "H4") (pin "11") (pinfunction "11_11") (pintype "passive+no_connect"))
    )
    (net (code "91") (name "unconnected-(M-Pad8)") (class "Default")
      (node (ref "M") (pin "8") (pinfunction "8_8") (pintype "passive"))
    )
    (net (code "92") (name "unconnected-(M-Pad9)") (class "Default")
      (node (ref "M") (pin "9") (pinfunction "9_9") (pintype "passive"))
    )
    (net (code "93") (name "unconnected-(M-Pad13)") (class "Default")
      (node (ref "M") (pin "13") (pinfunction "13_13") (pintype "passive"))
    )
    (net (code "94") (name "unconnected-(M-Pad14)") (class "Default")
      (node (ref "M") (pin "14") (pinfunction "14_14") (pintype "passive"))
    )
    (net (code "95") (name "unconnected-(N1-Pad6)") (class "Default")
      (node (ref "N1") (pin "6") (pinfunction "6_6") (pintype "passive+no_connect"))
    )
    (net (code "96") (name "unconnected-(N2-Pad6)") (class "Default")
      (node (ref "N2") (pin "6") (pinfunction "6_6") (pintype "passive+no_connect"))
    )
    (net (code "97") (name "unconnected-(N2-Pad11)") (class "Default")
      (node (ref "N2") (pin "11") (pinfunction "11_11") (pintype "passive+no_connect"))
    )
    (net (code "98") (name "unconnected-(N4-Pad6)") (class "Default")
      (node (ref "N4") (pin "6") (pinfunction "6_6") (pintype "passive"))
    )
    (net (code "99") (name "unconnected-(N4-Pad9)") (class "Default")
      (node (ref "N4") (pin "9") (pinfunction "9_9") (pintype "passive+no_connect"))
    )
    (net (code "100") (name "unconnected-(P1-Pad1)") (class "Default")
      (node (ref "P1") (pin "1") (pinfunction "1_1") (pintype "passive"))
    )
    (net (code "101") (name "unconnected-(U2-Pad1)") (class "Default")
      (node (ref "U2") (pin "1") (pinfunction "1_1") (pintype "passive"))
    )
    (net (code "102") (name "unconnected-(U2-Pad5)") (class "Default")
      (node (ref "U2") (pin "5") (pinfunction "5_5") (pintype "passive"))
    )
    (net (code "103") (name "unconnected-(U2-Pad8)") (class "Default")
      (node (ref "U2") (pin "8") (pinfunction "8_8") (pintype "passive"))
    )
  )
)
